# ModuloAutomacao.net
KiCad netlist of a schematic drawn in EAGLE
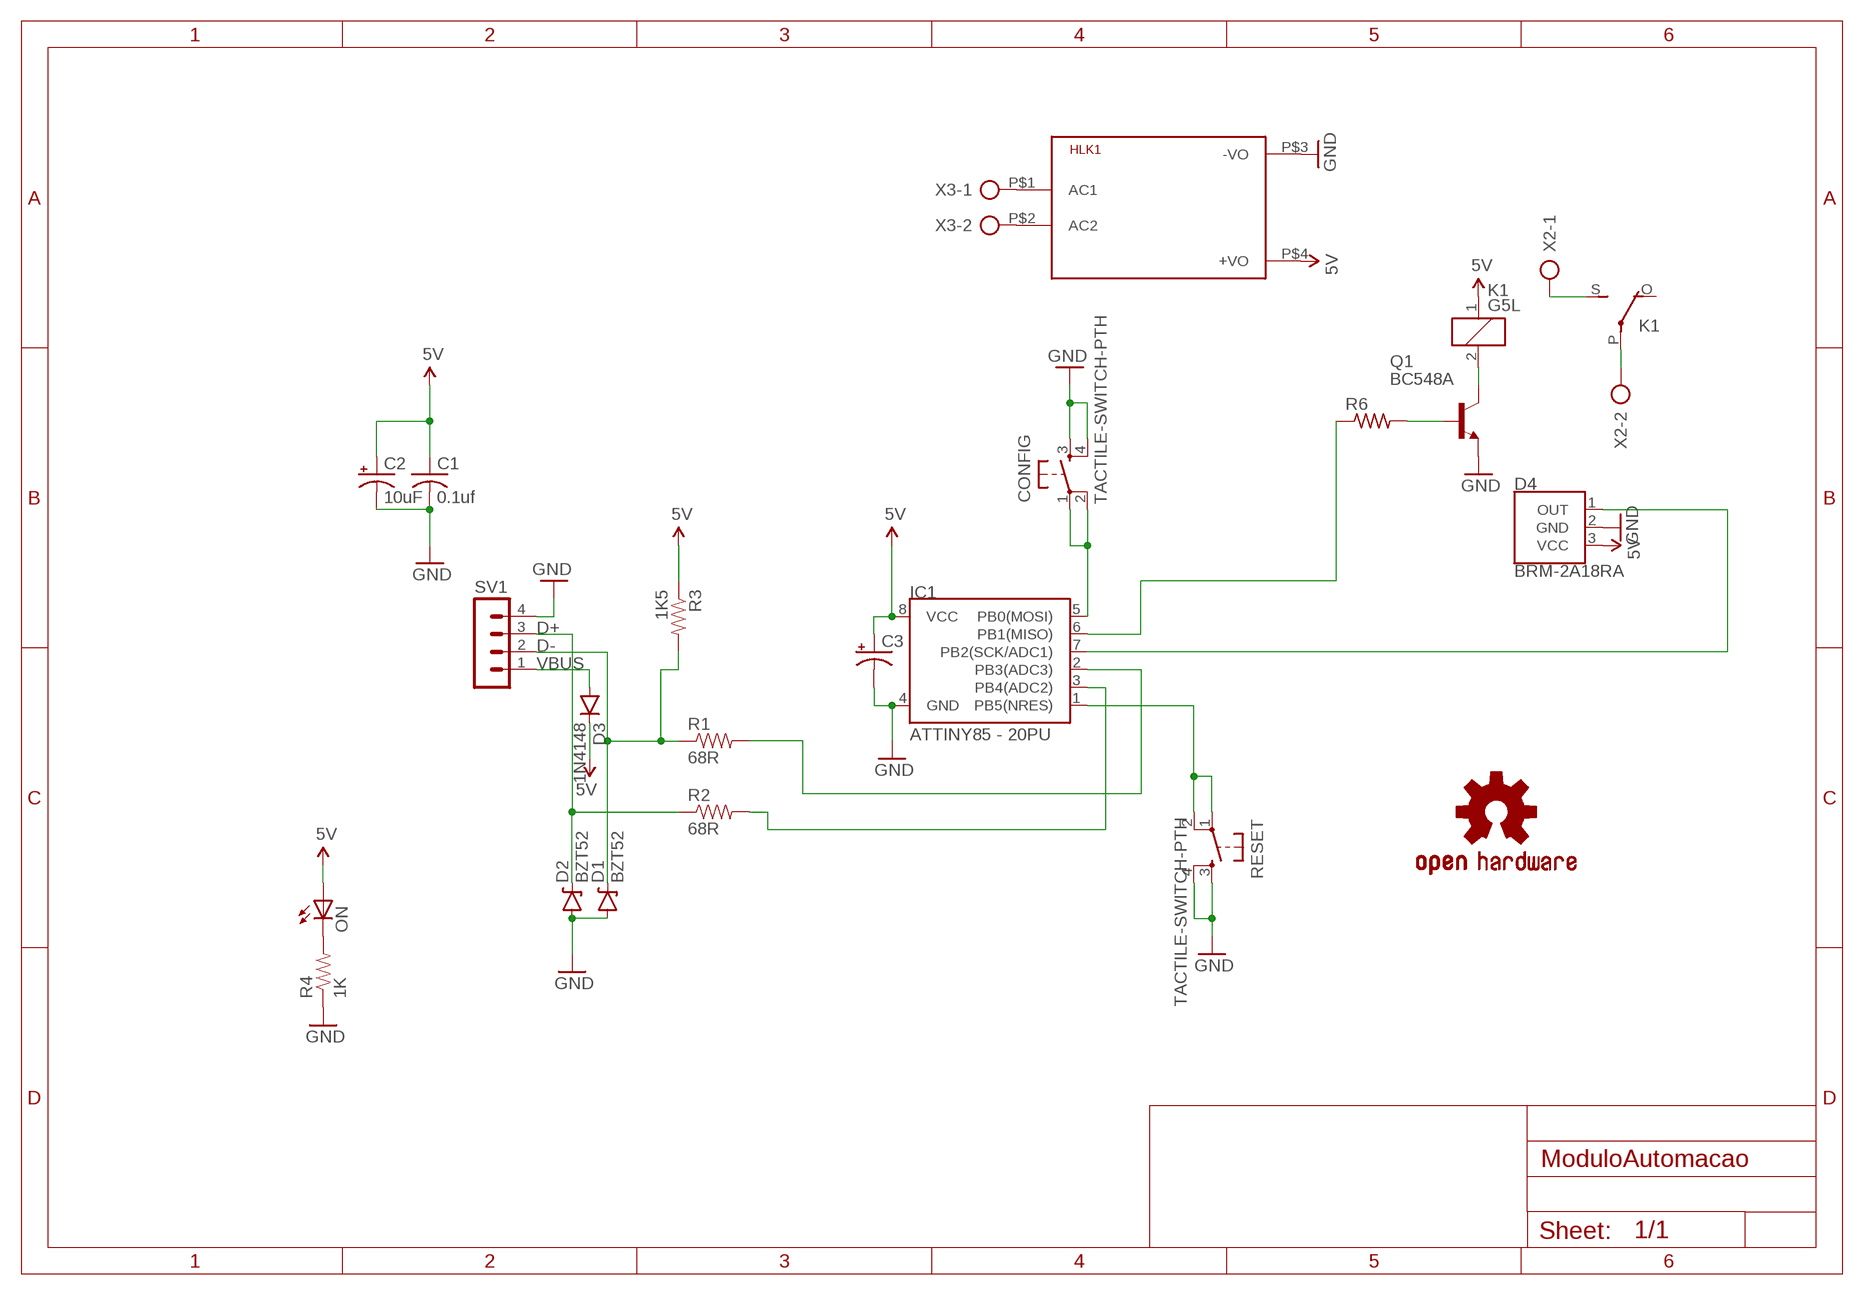
[diagram p0: schematic, sheet 1]

(export (version "E")
  (design (tool "Eeschema 10.0.6"))
  (components
    (comp (ref "C1")
      (value "0.1uf")
      (footprint "eagle-import:C025-025X050")
      (libsource (lib "eagle-import") (part "C-US025-025X050"))
    )
    (comp (ref "C2")
      (value "10uF")
      (footprint "eagle-import:E2,5-6E")
      (libsource (lib "eagle-import") (part "CPOL-USE2,5-6E"))
    )
    (comp (ref "C3")
      (value "CPOL-USE1.8-4")
      (footprint "eagle-import:E1,8-4")
      (libsource (lib "eagle-import") (part "rcl_334_CPOL-USE1.8-4"))
    )
    (comp (ref "CONFIG")
      (value "TACTILE-SWITCH-PTH")
      (footprint "eagle-import:TAC-SWITCH-PTH")
      (libsource (lib "eagle-import") (part "TACTILE-SWITCH-PTH"))
    )
    (comp (ref "D1")
      (value "BZT52")
      (footprint "eagle-import:DIODE-BZT52")
      (libsource (lib "eagle-import") (part "DIODE-ZENER"))
    )
    (comp (ref "D2")
      (value "BZT52")
      (footprint "eagle-import:DIODE-BZT52")
      (libsource (lib "eagle-import") (part "DIODE-ZENER"))
    )
    (comp (ref "D3")
      (value "1N4148")
      (footprint "eagle-import:DIODE-1N4148")
      (libsource (lib "eagle-import") (part "DIODE1N4148"))
    )
    (comp (ref "D4")
      (value "BRM-2A18RA")
      (footprint "eagle-import:BRM-2508")
      (libsource (lib "eagle-import") (part "BRM-2A18RA"))
    )
    (comp (ref "HLK1")
      (value "HLK-PM013W")
      (footprint "eagle-import:HLK-PM01")
      (libsource (lib "eagle-import") (part "HLK-PM013W"))
    )
    (comp (ref "IC1")
      (value "ATTINY85 - 20PU")
      (footprint "eagle-import:DIP08")
      (libsource (lib "eagle-import") (part "ATTINY45TINY45-20-DIP"))
    )
    (comp (ref "K1")
      (value "G5L")
      (footprint "eagle-import:G5LE")
      (libsource (lib "eagle-import") (part "G5L"))
    )
    (comp (ref "LOGO1")
      (value "OSHW-LOGOM")
      (footprint "eagle-import:OSHW-LOGO-M")
      (libsource (lib "eagle-import") (part "OSHW-LOGOM"))
    )
    (comp (ref "ON")
      (value "LED3MM")
      (footprint "eagle-import:LED3MM")
      (libsource (lib "eagle-import") (part "LED3MM"))
    )
    (comp (ref "Q1")
      (value "BC548A")
      (footprint "eagle-import:TO92-EBC")
      (libsource (lib "eagle-import") (part "BC548A"))
    )
    (comp (ref "R1")
      (value "68R")
      (footprint "eagle-import:AXIAL-0.4")
      (libsource (lib "eagle-import") (part "RESISTORPTH-1/4W"))
    )
    (comp (ref "R2")
      (value "68R")
      (footprint "eagle-import:AXIAL-0.4")
      (libsource (lib "eagle-import") (part "RESISTORPTH-1/4W"))
    )
    (comp (ref "R3")
      (value "1K5")
      (footprint "eagle-import:AXIAL-0.4")
      (libsource (lib "eagle-import") (part "RESISTORPTH-1/4W"))
    )
    (comp (ref "R4")
      (value "1K")
      (footprint "eagle-import:AXIAL-0.4")
      (libsource (lib "eagle-import") (part "RESISTORPTH-1/4W"))
    )
    (comp (ref "R6")
      (value "R-US_0204/7")
      (footprint "eagle-import:0204_7")
      (libsource (lib "eagle-import") (part "R-US_0204/7"))
    )
    (comp (ref "RESET")
      (value "TACTILE-SWITCH-PTH")
      (footprint "eagle-import:TAC-SWITCH-PTH")
      (libsource (lib "eagle-import") (part "TACTILE-SWITCH-PTH"))
    )
    (comp (ref "SV1")
      (value "MA04-1")
      (footprint "eagle-import:MA04-1")
      (libsource (lib "eagle-import") (part "MA04-1"))
    )
    (comp (ref "X2")
      (value "AK300/2")
      (footprint "eagle-import:AK300_2")
      (libsource (lib "eagle-import") (part "AK300/2"))
    )
    (comp (ref "X3")
      (value "AK300/2")
      (footprint "eagle-import:AK300_2")
      (libsource (lib "eagle-import") (part "AK300/2"))
    )
  )
  (nets
    (net (code "1") (name "/D+") (class "Default")
      (node (ref "D2") (pin "C") (pinfunction "C_C") (pintype "passive"))
      (node (ref "R2") (pin "P$1") (pinfunction "1_P$1") (pintype "passive"))
      (node (ref "SV1") (pin "3") (pinfunction "3_3") (pintype "passive"))
    )
    (net (code "2") (name "/D-") (class "Default")
      (node (ref "D1") (pin "C") (pinfunction "C_C") (pintype "passive"))
      (node (ref "R1") (pin "P$1") (pinfunction "1_P$1") (pintype "passive"))
      (node (ref "R3") (pin "P$2") (pinfunction "2_P$2") (pintype "passive"))
      (node (ref "SV1") (pin "2") (pinfunction "2_2") (pintype "passive"))
    )
    (net (code "3") (name "/VBUS") (class "Default")
      (node (ref "D3") (pin "A") (pinfunction "A_A") (pintype "passive"))
      (node (ref "SV1") (pin "1") (pinfunction "1_1") (pintype "passive"))
    )
    (net (code "4") (name "5V") (class "Default")
      (node (ref "C1") (pin "1") (pinfunction "1_1") (pintype "passive"))
      (node (ref "C2") (pin "+") (pinfunction "+_+") (pintype "passive"))
      (node (ref "C3") (pin "+") (pinfunction "+_+") (pintype "passive"))
      (node (ref "D3") (pin "C") (pinfunction "C_C") (pintype "passive"))
      (node (ref "D4") (pin "3") (pinfunction "VCC_3") (pintype "bidirectional"))
      (node (ref "HLK1") (pin "P$4") (pinfunction "+VO_P$4") (pintype "bidirectional"))
      (node (ref "IC1") (pin "8") (pinfunction "VCC_8") (pintype "bidirectional"))
      (node (ref "K1") (pin "1") (pinfunction "1_1") (pintype "passive"))
      (node (ref "ON") (pin "A") (pinfunction "A_A") (pintype "passive"))
      (node (ref "R3") (pin "P$1") (pinfunction "1_P$1") (pintype "passive"))
    )
    (net (code "5") (name "GND") (class "Default")
      (node (ref "C1") (pin "2") (pinfunction "2_2") (pintype "passive"))
      (node (ref "C2") (pin "-") (pinfunction "-_-") (pintype "passive"))
      (node (ref "C3") (pin "-") (pinfunction "-_-") (pintype "passive"))
      (node (ref "CONFIG") (pin "3") (pinfunction "3_3") (pintype "passive"))
      (node (ref "CONFIG") (pin "4") (pinfunction "4_4") (pintype "passive"))
      (node (ref "D1") (pin "A") (pinfunction "A_A") (pintype "passive"))
      (node (ref "D2") (pin "A") (pinfunction "A_A") (pintype "passive"))
      (node (ref "D4") (pin "2") (pinfunction "GND_2") (pintype "bidirectional"))
      (node (ref "HLK1") (pin "P$3") (pinfunction "-VO_P$3") (pintype "bidirectional"))
      (node (ref "IC1") (pin "4") (pinfunction "GND_4") (pintype "bidirectional"))
      (node (ref "Q1") (pin "E") (pinfunction "E_E") (pintype "passive"))
      (node (ref "R4") (pin "P$1") (pinfunction "1_P$1") (pintype "passive"))
      (node (ref "RESET") (pin "3") (pinfunction "3_3") (pintype "passive"))
      (node (ref "RESET") (pin "4") (pinfunction "4_4") (pintype "passive"))
      (node (ref "SV1") (pin "4") (pinfunction "4_4") (pintype "passive"))
    )
    (net (code "6") (name "Net-(D4-OUT)") (class "Default")
      (node (ref "D4") (pin "1") (pinfunction "OUT_1") (pintype "bidirectional"))
      (node (ref "IC1") (pin "7") (pinfunction "PB2(SCK/ADC1)_7") (pintype "bidirectional"))
    )
    (net (code "7") (name "Net-(HLK1-AC1)") (class "Default")
      (node (ref "HLK1") (pin "P$1") (pinfunction "AC1_P$1") (pintype "bidirectional"))
      (node (ref "X3") (pin "1") (pinfunction "KL_1") (pintype "passive"))
    )
    (net (code "8") (name "Net-(HLK1-AC2)") (class "Default")
      (node (ref "HLK1") (pin "P$2") (pinfunction "AC2_P$2") (pintype "bidirectional"))
      (node (ref "X3") (pin "2") (pinfunction "KL_2") (pintype "passive"))
    )
    (net (code "9") (name "Net-(IC1-PB0(MOSI))") (class "Default")
      (node (ref "CONFIG") (pin "1") (pinfunction "1_1") (pintype "passive"))
      (node (ref "CONFIG") (pin "2") (pinfunction "2_2") (pintype "passive"))
      (node (ref "IC1") (pin "5") (pinfunction "PB0(MOSI)_5") (pintype "bidirectional"))
    )
    (net (code "10") (name "Net-(IC1-PB1(MISO))") (class "Default")
      (node (ref "IC1") (pin "6") (pinfunction "PB1(MISO)_6") (pintype "bidirectional"))
      (node (ref "R6") (pin "1") (pinfunction "1_1") (pintype "passive"))
    )
    (net (code "11") (name "Net-(IC1-PB3(ADC3))") (class "Default")
      (node (ref "IC1") (pin "2") (pinfunction "PB3(ADC3)_2") (pintype "bidirectional"))
      (node (ref "R1") (pin "P$2") (pinfunction "2_P$2") (pintype "passive"))
    )
    (net (code "12") (name "Net-(IC1-PB4(ADC2))") (class "Default")
      (node (ref "IC1") (pin "3") (pinfunction "PB4(ADC2)_3") (pintype "bidirectional"))
      (node (ref "R2") (pin "P$2") (pinfunction "2_P$2") (pintype "passive"))
    )
    (net (code "13") (name "Net-(IC1-PB5(NRES))") (class "Default")
      (node (ref "IC1") (pin "1") (pinfunction "PB5(NRES)_1") (pintype "bidirectional"))
      (node (ref "RESET") (pin "1") (pinfunction "1_1") (pintype "passive"))
      (node (ref "RESET") (pin "2") (pinfunction "2_2") (pintype "passive"))
    )
    (net (code "14") (name "Net-(K1-Pad2)") (class "Default")
      (node (ref "K1") (pin "2") (pinfunction "2_2") (pintype "passive"))
      (node (ref "Q1") (pin "C") (pinfunction "C_C") (pintype "passive"))
    )
    (net (code "15") (name "Net-(ON-C)") (class "Default")
      (node (ref "ON") (pin "K") (pinfunction "C_K") (pintype "passive"))
      (node (ref "R4") (pin "P$2") (pinfunction "2_P$2") (pintype "passive"))
    )
    (net (code "16") (name "Net-(Q1-PadB)") (class "Default")
      (node (ref "Q1") (pin "B") (pinfunction "B_B") (pintype "passive"))
      (node (ref "R6") (pin "2") (pinfunction "2_2") (pintype "passive"))
    )
    (net (code "17") (name "Net-(X2A-KL)") (class "Default")
      (node (ref "K1") (pin "S") (pinfunction "S_S") (pintype "passive"))
      (node (ref "X2") (pin "1") (pinfunction "KL_1") (pintype "passive"))
    )
    (net (code "18") (name "Net-(X2B-KL)") (class "Default")
      (node (ref "K1") (pin "P") (pinfunction "P_P") (pintype "passive"))
      (node (ref "X2") (pin "2") (pinfunction "KL_2") (pintype "passive"))
    )
    (net (code "19") (name "unconnected-(K1-PadO)") (class "Default")
      (node (ref "K1") (pin "O") (pinfunction "O_O") (pintype "passive"))
    )
  )
)
